# LPEDT_revA1_bikeit_POWER_MECH.net
KiCad netlist of a schematic drawn in Altium Designer
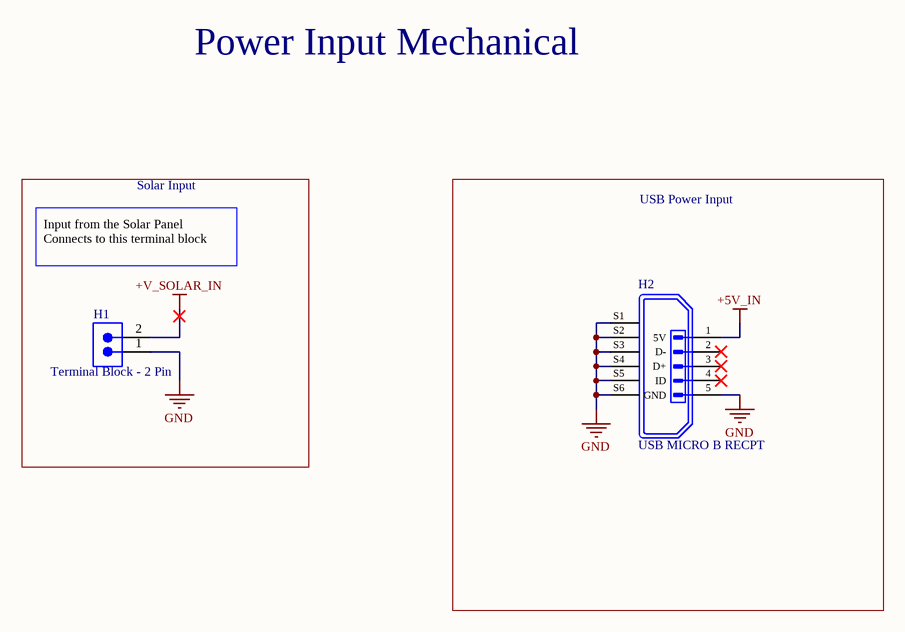
[diagram p0: LPEDT_revA1_bikeit_POWER_MECH.SchDoc]

(export (version "E")
  (design (tool "Eeschema 10.0.6"))
  (components
    (comp (ref "H1")
      (value "Terminal Block - 2 Pin")
      (description "TE CONNECTIVITY / BUCHANAN - 282834-2 - TERMINAL BLOCK, WIRE TO BRD, 2POS, 16AWG")
      (fields
        (field (name "MANUFACTURER") "TE Connectivity")
        (field (name "MANUFACTURER PART NUMBER") "282834-2")
      )
      (libsource (lib "LPEDT_revA1_bikeit_IL") (part "282834-2"))
    )
    (comp (ref "H2")
      (value "USB MICRO B RECPT")
      (footprint "AMPHENOL_10118194-0001LF")
      (description "USB - micro B USB 2.0 Receptacle Connector 5 Position Surface Mount, Right Angle; Through Hole")
      (fields
        (field (name "MANUFACTURER") "Amphenol FCI")
        (field (name "MANUFACTURER PART NUMBER") "10118194-0001LF")
      )
      (libsource (lib "LPEDT_revA1_bikeit") (part "10118194-0001LF"))
    )
  )
  (nets
    (net (code "1") (name "+5V_IN") (class "Default")
      (node (ref "H2") (pin "1") (pinfunction "5V_1") (pintype "power_in"))
    )
    (net (code "2") (name "+V_SOLAR_IN") (class "Default")
      (node (ref "H1") (pin "2") (pinfunction "+_2") (pintype "passive"))
    )
    (net (code "3") (name "GND") (class "Default")
      (node (ref "H1") (pin "1") (pinfunction "-_1") (pintype "passive"))
      (node (ref "H2") (pin "5") (pinfunction "GND_5") (pintype "passive"))
      (node (ref "H2") (pin "S1") (pinfunction "S1_S1") (pintype "passive"))
      (node (ref "H2") (pin "S2") (pinfunction "S2_S2") (pintype "passive"))
      (node (ref "H2") (pin "S3") (pinfunction "S3_S3") (pintype "passive"))
      (node (ref "H2") (pin "S4") (pinfunction "S4_S4") (pintype "passive"))
      (node (ref "H2") (pin "S5") (pinfunction "S5_S5") (pintype "passive"))
      (node (ref "H2") (pin "S6") (pinfunction "S6_S6") (pintype "passive"))
    )
    (net (code "4") (name "unconnected-(H2-D+-Pad3)") (class "Default")
      (node (ref "H2") (pin "3") (pinfunction "D+_3") (pintype "passive+no_connect"))
    )
    (net (code "5") (name "unconnected-(H2-D--Pad2)") (class "Default")
      (node (ref "H2") (pin "2") (pinfunction "D-_2") (pintype "passive+no_connect"))
    )
    (net (code "6") (name "unconnected-(H2-ID-Pad4)") (class "Default")
      (node (ref "H2") (pin "4") (pinfunction "ID_4") (pintype "passive+no_connect"))
    )
  )
)
